# flexi_ethernet_w5500.net
KiCad netlist of a schematic drawn in Altium Designer
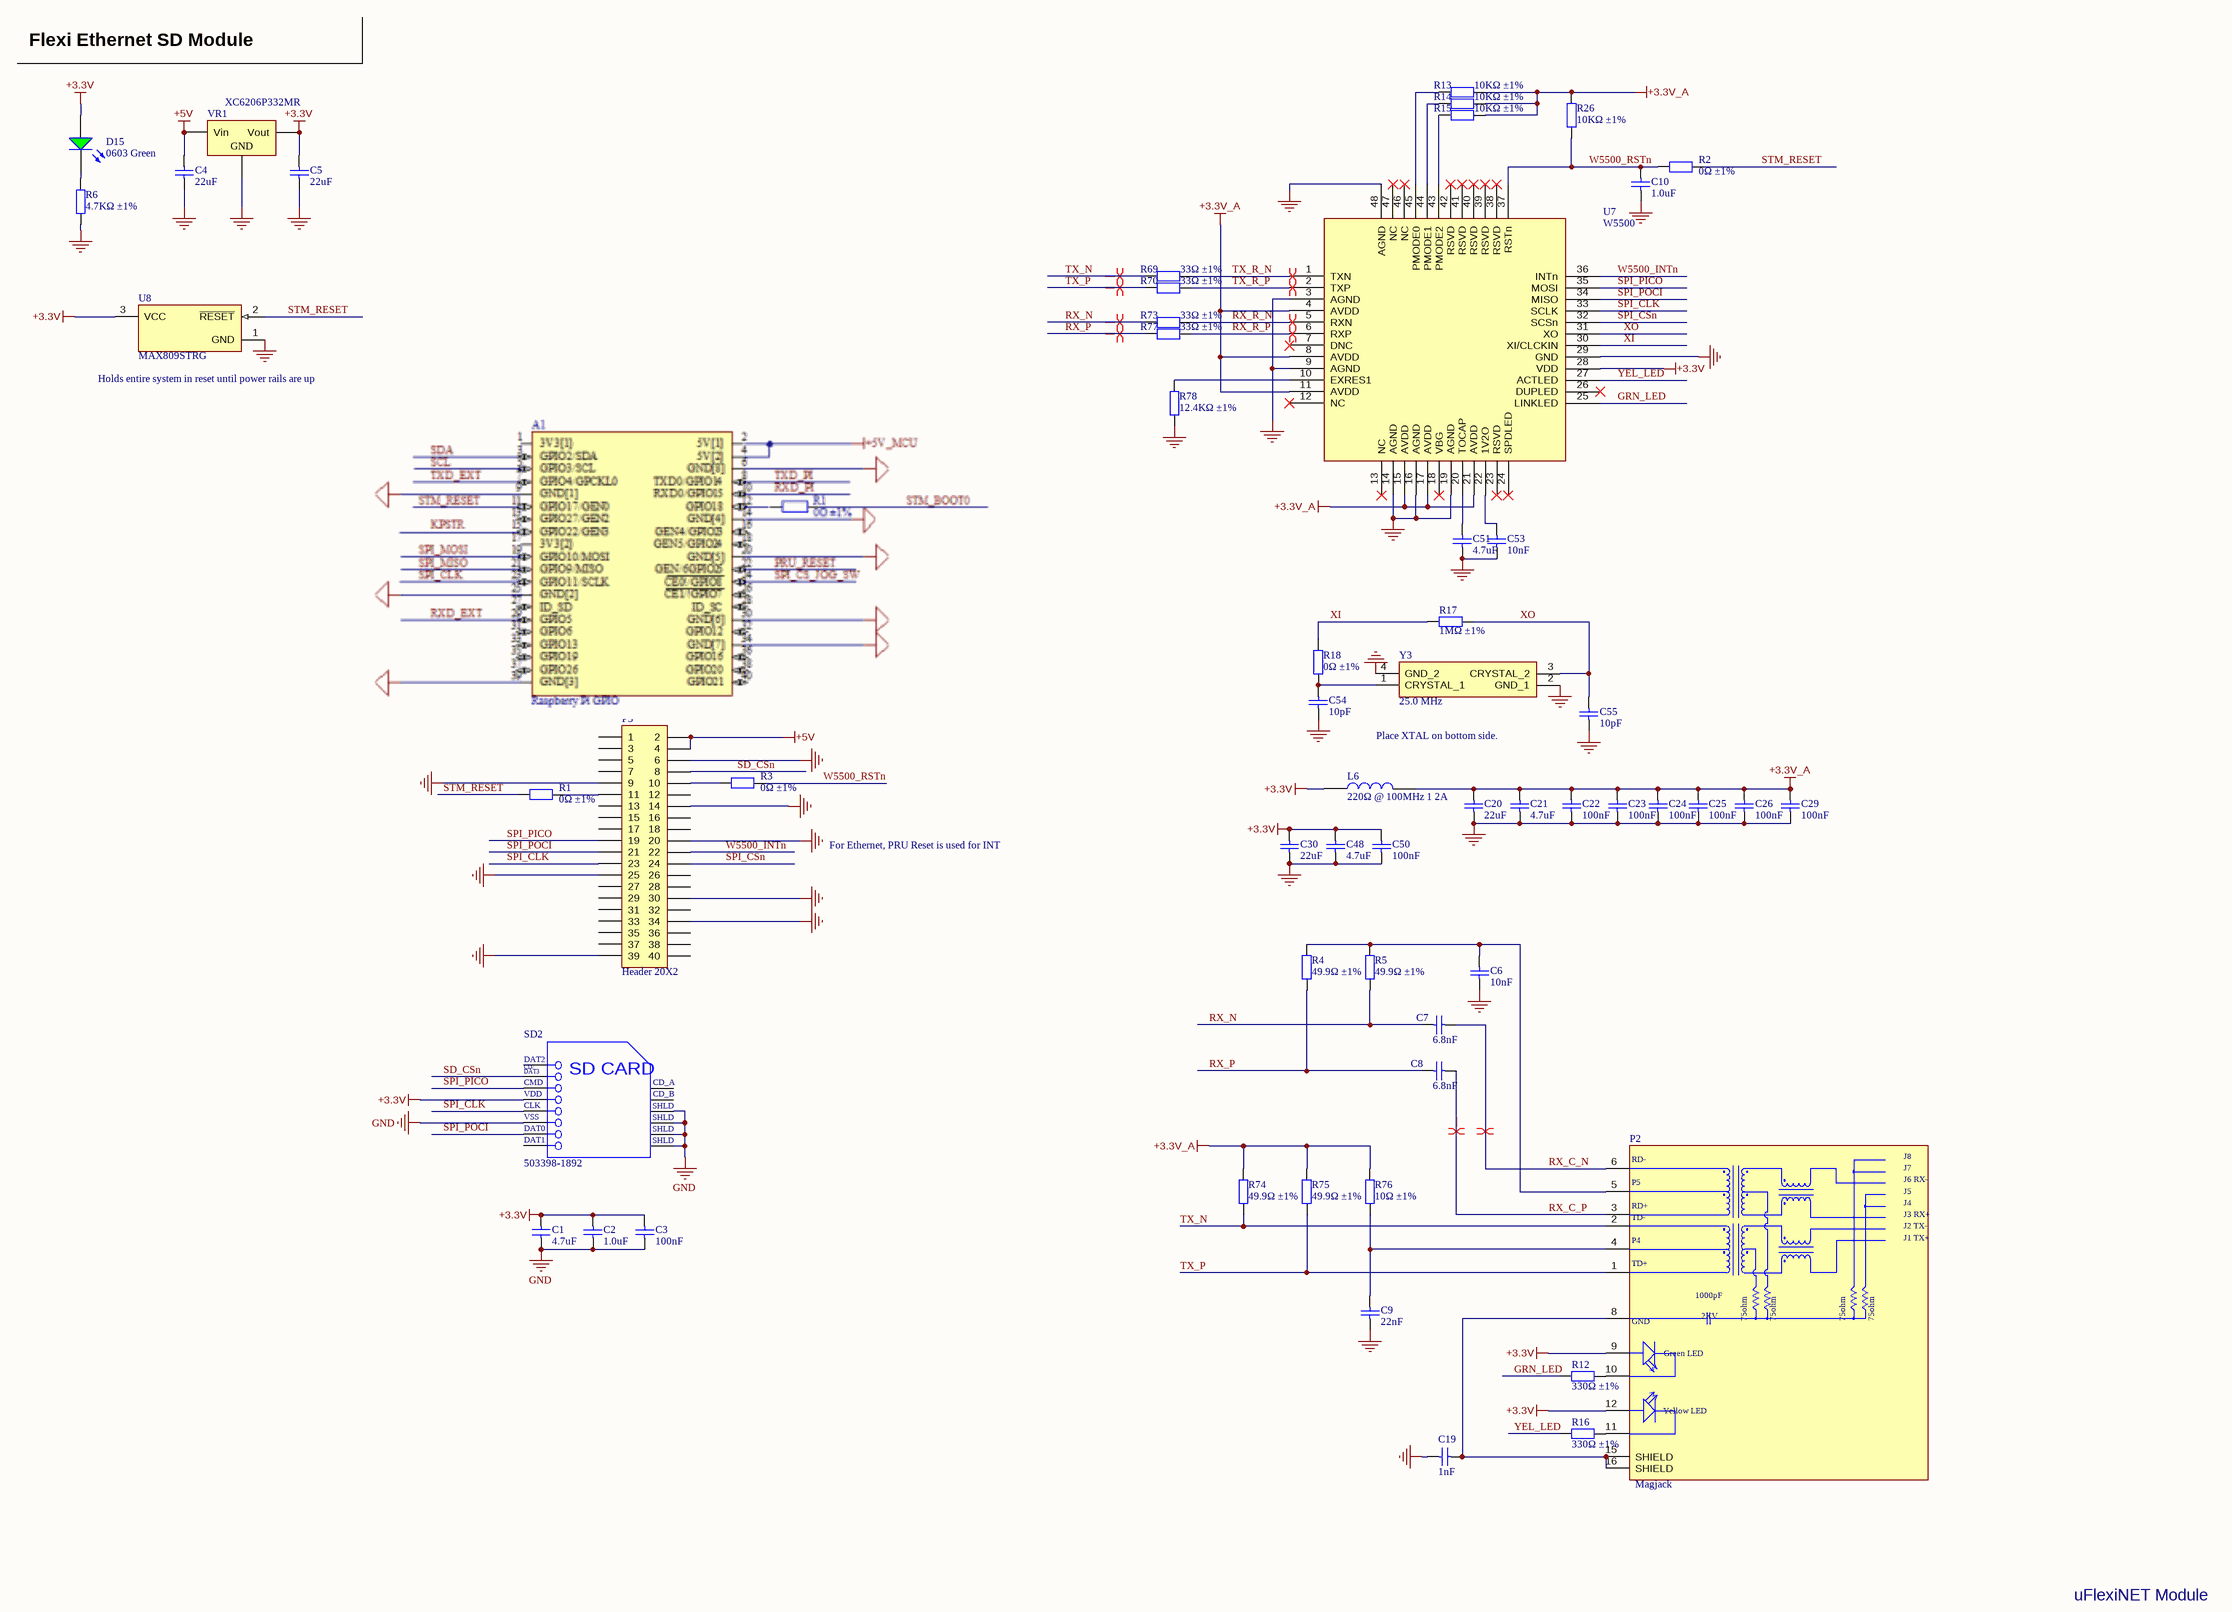
[diagram p0: flexi_ethernet_w5500.SchDoc]

(export (version "E")
  (design (tool "Eeschema 10.0.6"))
  (components
    (comp (ref "C1")
      (value "4.7uF")
      (footprint "0603_C")
      (description "Chip capacitors")
      (fields
        (field (name "MANUFACTURER") "Samsung Electro-Mechanics")
        (field (name "PARTNUMBER") "CL10A475KO8NNNC")
      )
      (libsource (lib "Cap") (part "0603 4.7uF (475) 10% 16V"))
    )
    (comp (ref "C2")
      (value "1.0uF")
      (footprint "0402_C")
      (description "Chip capacitor")
      (fields (field (name "MANUFACTURER") "Samsung Electro-Mechanics") (field (name "TOLERANCE") "10%"))
      (libsource (lib "Cap") (part "0402 1.0uF (105) 10% 25V"))
    )
    (comp (ref "C3")
      (value "100nF")
      (footprint "0402_C")
      (description "Chip capacitors")
      (fields (field (name "MANUFACTURER") "Samsung Electro-Mechanics") (field (name "TOLERANCE") "10%"))
      (libsource (lib "Cap") (part "0402 100nF (104) 10% 16V"))
    )
    (comp (ref "C4")
      (value "22uF")
      (footprint "0805_C")
      (description "Chip capacitors")
      (fields
        (field (name "MANUFACTURER") "Samsung Electro-Mechanics")
        (field (name "PARTNUMBER") "CL21A226MAQNNNE")
      )
      (libsource (lib "Cap") (part "0805 22uF (226) 20% 25V"))
    )
    (comp (ref "C5")
      (value "22uF")
      (footprint "0805_C")
      (description "Chip capacitors")
      (fields
        (field (name "MANUFACTURER") "Samsung Electro-Mechanics")
        (field (name "PARTNUMBER") "CL21A226MAQNNNE")
      )
      (libsource (lib "Cap") (part "0805 22uF (226) 20% 25V"))
    )
    (comp (ref "C6")
      (value "10nF")
      (footprint "0402_C")
      (description "Chip capacitors")
      (fields
        (field (name "MANUFACTURER") "Samsung Electro-Mechanics")
        (field (name "PARTNUMBER") "CL05B103KB5NNNC")
      )
      (libsource (lib "Cap") (part "0402 10nF (103) 10% 50V"))
    )
    (comp (ref "C7")
      (value "6.8nF")
      (footprint "0402_C")
      (description "Chip capacitors")
      (fields
        (field (name "MANUFACTURER") "Guangdong Fenghua Advanced Tech")
        (field (name "PARTNUMBER") "0402B682K500NT")
      )
      (libsource (lib "Cap") (part "0402 6.8nF (682) 10% 50V"))
    )
    (comp (ref "C8")
      (value "6.8nF")
      (footprint "0402_C")
      (description "Chip capacitors")
      (fields
        (field (name "MANUFACTURER") "Guangdong Fenghua Advanced Tech")
        (field (name "PARTNUMBER") "0402B682K500NT")
      )
      (libsource (lib "Cap") (part "0402 6.8nF (682) 10% 50V"))
    )
    (comp (ref "C9")
      (value "22nF")
      (footprint "0402_C")
      (description "Chip capacitors")
      (fields
        (field (name "MANUFACTURER") "Guangdong Fenghua Advanced Tech")
        (field (name "PARTNUMBER") "0402B223K500NT")
      )
      (libsource (lib "Cap") (part "0402 22nF (223) 10% 50V"))
    )
    (comp (ref "C10")
      (value "1.0uF")
      (footprint "0402_C")
      (description "Chip capacitor")
      (fields (field (name "MANUFACTURER") "Samsung Electro-Mechanics") (field (name "TOLERANCE") "10%"))
      (libsource (lib "Cap") (part "0402 1.0uF (105) 10% 25V"))
    )
    (comp (ref "C19")
      (value "1nF")
      (footprint "1206_C")
      (description "Chip capacitors")
      (fields
        (field (name "MANUFACTURER") "Samsung Electro-Mechanics")
        (field (name "PARTNUMBER") "CL31B102KGFNNNE")
      )
      (libsource (lib "Cap") (part "1206 1nF (102) 10% 500V"))
    )
    (comp (ref "C20")
      (value "22uF")
      (footprint "0805_C")
      (description "Chip capacitors")
      (fields
        (field (name "MANUFACTURER") "Samsung Electro-Mechanics")
        (field (name "PARTNUMBER") "CL21A226MAQNNNE")
      )
      (libsource (lib "Cap") (part "0805 22uF (226) 20% 25V"))
    )
    (comp (ref "C21")
      (value "4.7uF")
      (footprint "0603_C")
      (description "Chip capacitors")
      (fields
        (field (name "MANUFACTURER") "Samsung Electro-Mechanics")
        (field (name "PARTNUMBER") "CL10A475KO8NNNC")
      )
      (libsource (lib "Cap") (part "0603 4.7uF (475) 10% 16V"))
    )
    (comp (ref "C22")
      (value "100nF")
      (footprint "0402_C")
      (description "Chip capacitors")
      (fields
        (field (name "MANUFACTURER") "Samsung Electro-Mechanics")
        (field (name "PARTNUMBER") "CL05B104KO5NNNC")
      )
      (libsource (lib "Cap") (part "0402 100nF (104) 10% 16V"))
    )
    (comp (ref "C23")
      (value "100nF")
      (footprint "0402_C")
      (description "Chip capacitors")
      (fields
        (field (name "MANUFACTURER") "Samsung Electro-Mechanics")
        (field (name "PARTNUMBER") "CL05B104KO5NNNC")
      )
      (libsource (lib "Cap") (part "0402 100nF (104) 10% 16V"))
    )
    (comp (ref "C24")
      (value "100nF")
      (footprint "0402_C")
      (description "Chip capacitors")
      (fields
        (field (name "MANUFACTURER") "Samsung Electro-Mechanics")
        (field (name "PARTNUMBER") "CL05B104KO5NNNC")
      )
      (libsource (lib "Cap") (part "0402 100nF (104) 10% 16V"))
    )
    (comp (ref "C25")
      (value "100nF")
      (footprint "0402_C")
      (description "Chip capacitors")
      (fields
        (field (name "MANUFACTURER") "Samsung Electro-Mechanics")
        (field (name "PARTNUMBER") "CL05B104KO5NNNC")
      )
      (libsource (lib "Cap") (part "0402 100nF (104) 10% 16V"))
    )
    (comp (ref "C26")
      (value "100nF")
      (footprint "0402_C")
      (description "Chip capacitors")
      (fields
        (field (name "MANUFACTURER") "Samsung Electro-Mechanics")
        (field (name "PARTNUMBER") "CL05B104KO5NNNC")
      )
      (libsource (lib "Cap") (part "0402 100nF (104) 10% 16V"))
    )
    (comp (ref "C29")
      (value "100nF")
      (footprint "0402_C")
      (description "Chip capacitors")
      (fields
        (field (name "MANUFACTURER") "Samsung Electro-Mechanics")
        (field (name "PARTNUMBER") "CL05B104KO5NNNC")
      )
      (libsource (lib "Cap") (part "0402 100nF (104) 10% 16V"))
    )
    (comp (ref "C30")
      (value "22uF")
      (footprint "0805_C")
      (description "Chip capacitors")
      (fields
        (field (name "MANUFACTURER") "Samsung Electro-Mechanics")
        (field (name "PARTNUMBER") "CL21A226MAQNNNE")
      )
      (libsource (lib "Cap") (part "0805 22uF (226) 20% 25V"))
    )
    (comp (ref "C48")
      (value "4.7uF")
      (footprint "0603_C")
      (description "Chip capacitors")
      (fields
        (field (name "MANUFACTURER") "Samsung Electro-Mechanics")
        (field (name "PARTNUMBER") "CL10A475KO8NNNC")
      )
      (libsource (lib "Cap") (part "0603 4.7uF (475) 10% 16V"))
    )
    (comp (ref "C50")
      (value "100nF")
      (footprint "0402_C")
      (description "Chip capacitors")
      (fields
        (field (name "MANUFACTURER") "Samsung Electro-Mechanics")
        (field (name "PARTNUMBER") "CL05B104KO5NNNC")
      )
      (libsource (lib "Cap") (part "0402 100nF (104) 10% 16V"))
    )
    (comp (ref "C51")
      (value "4.7uF")
      (footprint "0402_C")
      (description "Chip capacitor")
      (fields
        (field (name "MANUFACTURER") "Samsung Electro-Mechanics")
        (field (name "PARTNUMBER") "CL05A475MP5NRNC")
      )
      (libsource (lib "Cap") (part "0402 4.7uF (475) 20% 10V"))
    )
    (comp (ref "C53")
      (value "10nF")
      (footprint "0402_C")
      (description "Chip capacitors")
      (fields
        (field (name "MANUFACTURER") "Samsung Electro-Mechanics")
        (field (name "PARTNUMBER") "CL05B103KB5NNNC")
      )
      (libsource (lib "Cap") (part "0402 10nF (103) 10% 50V"))
    )
    (comp (ref "C54")
      (value "10pF")
      (footprint "0402_C")
      (description "Chip capacitors")
      (fields
        (field (name "MANUFACTURER") "Samsung Electro-Mechanics")
        (field (name "PARTNUMBER") "CL05C100JB5NNNC")
      )
      (libsource (lib "Cap") (part "0402 10pF (100) 5% 50V"))
    )
    (comp (ref "C55")
      (value "10pF")
      (footprint "0402_C")
      (description "Chip capacitors")
      (fields
        (field (name "MANUFACTURER") "Samsung Electro-Mechanics")
        (field (name "PARTNUMBER") "CL05C100JB5NNNC")
      )
      (libsource (lib "Cap") (part "0402 10pF (100) 5% 50V"))
    )
    (comp (ref "D15")
      (value "0603 Green")
      (footprint "0603_LED_S1")
      (description "LED")
      (libsource (lib "LED") (part "0603 LED Green"))
    )
    (comp (ref "L6")
      (value "220Ω @ 100MHz 1 2A")
      (footprint "0805_C")
      (description "220Ω @ 100MHz 1 2A 150mΩ 0805 Ferrite Beads ROHS")
      (libsource (lib "FBEAD") (part "0402 220R@100Mhz 0.1A"))
    )
    (comp (ref "P2")
      (value "Magjack")
      (footprint "HANRUN_HR911105A")
      (description "HR911105A Ethernet Interface Arduino Platform Evaluation Expansion Board")
      (fields (field (name "MP") "HR911105A") (field (name "MF") "DFRobot"))
      (libsource (lib "PrintNC_GRBLHAL_Breakout") (part "HR911105A"))
    )
    (comp (ref "P3")
      (value "Header 20X2")
      (footprint "HDR2X20_2.54_180")
      (description "Header, 20-Pin, Dual row")
      (fields (field (name "PUBLISHER") "Altium Limited"))
      (libsource (lib "Miscellaneous Connectors") (part "Header 20X2"))
    )
    (comp (ref "R1")
      (value "0Ω ±1%")
      (footprint "0402_R")
      (description "Chip resistor")
      (fields (field (name "MANUFACTURER") "Uniroyal Elec") (field (name "PARTNUMBER") "0402WGF0000TCE"))
      (libsource (lib "") (part "0402 0R (0R0) 1%_1"))
    )
    (comp (ref "R2")
      (value "0Ω ±1%")
      (footprint "0402_R")
      (description "Chip resistor")
      (fields (field (name "MANUFACTURER") "Uniroyal Elec") (field (name "PARTNUMBER") "0402WGF0000TCE"))
      (libsource (lib "") (part "0402 0R (0R0) 1%_1"))
    )
    (comp (ref "R3")
      (value "0Ω ±1%")
      (footprint "0402_R")
      (description "Chip resistor")
      (fields (field (name "MANUFACTURER") "Uniroyal Elec") (field (name "PARTNUMBER") "0402WGF0000TCE"))
      (libsource (lib "") (part "0402 0R (0R0) 1%_1"))
    )
    (comp (ref "R4")
      (value "49.9Ω ±1%")
      (footprint "0402_R")
      (description "Chip resistor")
      (fields (field (name "MANUFACTURER") "Uniroyal Elec") (field (name "PARTNUMBER") "0402WGF499JTCE"))
      (libsource (lib "RES") (part "0402 49.9R (49R9) 1%"))
    )
    (comp (ref "R5")
      (value "49.9Ω ±1%")
      (footprint "0402_R")
      (description "Chip resistor")
      (fields (field (name "MANUFACTURER") "Uniroyal Elec") (field (name "PARTNUMBER") "0402WGF499JTCE"))
      (libsource (lib "RES") (part "0402 49.9R (49R9) 1%"))
    )
    (comp (ref "R6")
      (value "4.7KΩ ±1%")
      (footprint "0402_R")
      (description "Chip resistor")
      (fields (field (name "MANUFACTURER") "Uniroyal Elec") (field (name "PARTNUMBER") "0402WGF4701TCE"))
      (libsource (lib "RES") (part "0402 4.7K (4701) 1%"))
    )
    (comp (ref "R12")
      (value "330Ω ±1%")
      (footprint "0402_R")
      (description "Chip resistor")
      (fields (field (name "MANUFACTURER") "Uniroyal Elec") (field (name "PARTNUMBER") "0402WGF3300TCE"))
      (libsource (lib "RES") (part "0402 330R (3300) 1%"))
    )
    (comp (ref "R13")
      (value "10KΩ ±1%")
      (footprint "0402_R")
      (description "Chip resistor")
      (fields (field (name "MANUFACTURER") "Uniroyal Elec") (field (name "PARTNUMBER") "0402WGF1002TCE"))
      (libsource (lib "RES") (part "0402 10K (1002) 1%"))
    )
    (comp (ref "R14")
      (value "10KΩ ±1%")
      (footprint "0402_R")
      (description "Chip resistor")
      (fields (field (name "MANUFACTURER") "Uniroyal Elec") (field (name "PARTNUMBER") "0402WGF1002TCE"))
      (libsource (lib "RES") (part "0402 10K (1002) 1%"))
    )
    (comp (ref "R15")
      (value "10KΩ ±1%")
      (footprint "0402_R")
      (description "Chip resistor")
      (fields (field (name "MANUFACTURER") "Uniroyal Elec") (field (name "PARTNUMBER") "0402WGF1002TCE"))
      (libsource (lib "RES") (part "0402 10K (1002) 1%"))
    )
    (comp (ref "R16")
      (value "330Ω ±1%")
      (footprint "0402_R")
      (description "Chip resistor")
      (fields (field (name "MANUFACTURER") "Uniroyal Elec") (field (name "PARTNUMBER") "0402WGF3300TCE"))
      (libsource (lib "RES") (part "0402 330R (3300) 1%"))
    )
    (comp (ref "R17")
      (value "1MΩ ±1%")
      (footprint "0402_R")
      (description "Chip resistor")
      (fields (field (name "MANUFACTURER") "Uniroyal Elec") (field (name "PARTNUMBER") "0402WGF1004TCE"))
      (libsource (lib "RES") (part "0402 1M (1004) 1%"))
    )
    (comp (ref "R18")
      (value "0Ω ±1%")
      (footprint "0402_R")
      (description "Chip resistor")
      (fields (field (name "MANUFACTURER") "Uniroyal Elec") (field (name "PARTNUMBER") "0402WGF0000TCE"))
      (libsource (lib "RES") (part "0402 0R (0R0) 1%"))
    )
    (comp (ref "R26")
      (value "10KΩ ±1%")
      (footprint "0402_R")
      (description "Chip resistor")
      (fields (field (name "MANUFACTURER") "Uniroyal Elec") (field (name "PARTNUMBER") "0402WGF1002TCE"))
      (libsource (lib "") (part "0402 10K (1002) 1%_1"))
    )
    (comp (ref "R69")
      (value "33Ω ±1%")
      (footprint "0402_R")
      (description "Chip resistor")
      (fields (field (name "MANUFACTURER") "Uniroyal Elec") (field (name "PARTNUMBER") "0402WGF330JTCE"))
      (libsource (lib "RES") (part "0402 33R (33R0) 1%"))
    )
    (comp (ref "R70")
      (value "33Ω ±1%")
      (footprint "0402_R")
      (description "Chip resistor")
      (fields (field (name "MANUFACTURER") "Uniroyal Elec") (field (name "PARTNUMBER") "0402WGF330JTCE"))
      (libsource (lib "RES") (part "0402 33R (33R0) 1%"))
    )
    (comp (ref "R73")
      (value "33Ω ±1%")
      (footprint "0402_R")
      (description "Chip resistor")
      (fields (field (name "MANUFACTURER") "Uniroyal Elec") (field (name "PARTNUMBER") "0402WGF330JTCE"))
      (libsource (lib "RES") (part "0402 33R (33R0) 1%"))
    )
    (comp (ref "R74")
      (value "49.9Ω ±1%")
      (footprint "0402_R")
      (description "Chip resistor")
      (fields (field (name "MANUFACTURER") "Uniroyal Elec") (field (name "PARTNUMBER") "0402WGF499JTCE"))
      (libsource (lib "RES") (part "0402 49.9R (49R9) 1%"))
    )
    (comp (ref "R75")
      (value "49.9Ω ±1%")
      (footprint "0402_R")
      (description "Chip resistor")
      (fields (field (name "MANUFACTURER") "Uniroyal Elec") (field (name "PARTNUMBER") "0402WGF499JTCE"))
      (libsource (lib "RES") (part "0402 49.9R (49R9) 1%"))
    )
    (comp (ref "R76")
      (value "10Ω ±1%")
      (footprint "0402_R")
      (description "Chip resistor")
      (fields (field (name "MANUFACTURER") "Uniroyal Elec") (field (name "PARTNUMBER") "0402WGF100JTCE"))
      (libsource (lib "RES") (part "0402 10R (10R0) 1%"))
    )
    (comp (ref "R77")
      (value "33Ω ±1%")
      (footprint "0402_R")
      (description "Chip resistor")
      (fields (field (name "MANUFACTURER") "Uniroyal Elec") (field (name "PARTNUMBER") "0402WGF330JTCE"))
      (libsource (lib "RES") (part "0402 33R (33R0) 1%"))
    )
    (comp (ref "R78")
      (value "12.4KΩ ±1%")
      (footprint "0603_R")
      (description "Chip resistor")
      (fields (field (name "MANUFACTURER") "Uniroyal Elec") (field (name "PARTNUMBER") "0603WAF1242T5E"))
      (libsource (lib "RES") (part "0603 10K (1002) 1%"))
    )
    (comp (ref "SD2")
      (value "503398-1892")
      (footprint "MOLX-503398-1892_V")
      (description "Micro SD Connector, Pitch 1.1 mm, 8 Position, Height 1.4 mm, -25 to 85 degC, RoHS, Tape and Reel")
      (fields (field (name "MANUFACTURER") "Molex"))
      (libsource (lib "Altium Content Vault") (part "CN-SD-8-2SW-4S"))
    )
    (comp (ref "U7")
      (value "W5500")
      (footprint "LQFP-48_7x7x05P")
      (description "Ethernet Controllers 2.97V ~ 3.63V 10/100 Base-T/TX PHY SPI LQFP-48_7x7x05P Ethernet ICs ROHS")
      (libsource (lib "IC") (part "W5500_[C32843]"))
    )
    (comp (ref "U8")
      (value "MAX809STRG")
      (footprint "FP-318-08-MFG")
      (description "IC MPU SUPERVISORY 2.93V SOT23")
      (fields
        (field (name "OCTOPART") "https://octopart.com/max809strg-on+semiconductor-509853")
        (field (name "MANUFACTURER") "ON SEMICONDUCTOR")
      )
      (libsource (lib "Altium Content Vault") (part "10e2fe7115e7b167e7ed62dcbcd754e"))
    )
    (comp (ref "VR1")
      (value "XC6206P332MR")
      (footprint "SOT-23-3L")
      (description "200mA 680mV@(100mA) Fixed 3.3V~3.3V Positive 1 6V SOT-23-3L Linear Voltage Regulators (LDO) ROHS")
      (libsource (lib "LDO") (part "SOT-23 XC6206P332MR"))
    )
    (comp (ref "Y3")
      (value "25.0 MHz")
      (footprint "SamacSys:YSX321SL")
      (description "Crystal or Oscillator")
      (fields (field (name "MANUFACTURER_PART_NUMBER") "X322525MSB4SI"))
      (libsource (lib "*") (part "YSX321SL"))
    )
  )
  (nets
    (net (code "1") (name "+3.3V") (class "Default")
      (node (ref "C1") (pin "2") (pinfunction "2_2") (pintype "passive"))
      (node (ref "C2") (pin "2") (pinfunction "2_2") (pintype "passive"))
      (node (ref "C3") (pin "2") (pinfunction "2_2") (pintype "passive"))
      (node (ref "C30") (pin "2") (pinfunction "2_2") (pintype "passive"))
      (node (ref "C48") (pin "2") (pinfunction "2_2") (pintype "passive"))
      (node (ref "C5") (pin "2") (pinfunction "2_2") (pintype "passive"))
      (node (ref "C50") (pin "2") (pinfunction "2_2") (pintype "passive"))
      (node (ref "D15") (pin "A") (pinfunction "A_A") (pintype "passive"))
      (node (ref "L6") (pin "1") (pinfunction "1_1") (pintype "passive"))
      (node (ref "P2") (pin "12") (pinfunction "YA_12") (pintype "passive"))
      (node (ref "P2") (pin "9") (pinfunction "GA_9") (pintype "passive"))
      (node (ref "SD2") (pin "4") (pinfunction "VDD_4") (pintype "passive"))
      (node (ref "U7") (pin "28") (pinfunction "VDD_28") (pintype "passive"))
      (node (ref "U8") (pin "3") (pinfunction "VCC_3") (pintype "power_in"))
      (node (ref "VR1") (pin "2") (pinfunction "Vout_2") (pintype "passive"))
    )
    (net (code "2") (name "+3.3V_A") (class "Default")
      (node (ref "C20") (pin "2") (pinfunction "2_2") (pintype "passive"))
      (node (ref "C21") (pin "2") (pinfunction "2_2") (pintype "passive"))
      (node (ref "C22") (pin "2") (pinfunction "2_2") (pintype "passive"))
      (node (ref "C23") (pin "2") (pinfunction "2_2") (pintype "passive"))
      (node (ref "C24") (pin "2") (pinfunction "2_2") (pintype "passive"))
      (node (ref "C25") (pin "2") (pinfunction "2_2") (pintype "passive"))
      (node (ref "C26") (pin "2") (pinfunction "2_2") (pintype "passive"))
      (node (ref "C29") (pin "2") (pinfunction "2_2") (pintype "passive"))
      (node (ref "L6") (pin "2") (pinfunction "2_2") (pintype "passive"))
      (node (ref "R13") (pin "1") (pinfunction "1_1") (pintype "passive"))
      (node (ref "R14") (pin "1") (pinfunction "1_1") (pintype "passive"))
      (node (ref "R15") (pin "1") (pinfunction "1_1") (pintype "passive"))
      (node (ref "R26") (pin "1") (pinfunction "1_1") (pintype "passive"))
      (node (ref "R74") (pin "1") (pinfunction "1_1") (pintype "passive"))
      (node (ref "R75") (pin "1") (pinfunction "1_1") (pintype "passive"))
      (node (ref "R76") (pin "1") (pinfunction "1_1") (pintype "passive"))
      (node (ref "U7") (pin "11") (pinfunction "AVDD_11") (pintype "passive"))
      (node (ref "U7") (pin "15") (pinfunction "AVDD_15") (pintype "passive"))
      (node (ref "U7") (pin "17") (pinfunction "AVDD_17") (pintype "passive"))
      (node (ref "U7") (pin "21") (pinfunction "AVDD_21") (pintype "passive"))
      (node (ref "U7") (pin "4") (pinfunction "AVDD_4") (pintype "passive"))
      (node (ref "U7") (pin "8") (pinfunction "AVDD_8") (pintype "passive"))
    )
    (net (code "3") (name "+5V") (class "Default")
      (node (ref "C4") (pin "2") (pinfunction "2_2") (pintype "passive"))
      (node (ref "P3") (pin "2") (pinfunction "2_2") (pintype "passive"))
      (node (ref "P3") (pin "4") (pinfunction "4_4") (pintype "passive"))
      (node (ref "VR1") (pin "3") (pinfunction "Vin_3") (pintype "passive"))
    )
    (net (code "4") (name "/GRN_LED") (class "Default")
      (node (ref "R12") (pin "1") (pinfunction "1_1") (pintype "passive"))
      (node (ref "U7") (pin "25") (pinfunction "LINKLED_25") (pintype "passive"))
    )
    (net (code "5") (name "/RX_C_N") (class "Default")
      (node (ref "C7") (pin "1") (pinfunction "1_1") (pintype "passive"))
      (node (ref "P2") (pin "6") (pinfunction "RD-_6") (pintype "passive"))
    )
    (net (code "6") (name "/RX_C_P") (class "Default")
      (node (ref "C8") (pin "1") (pinfunction "1_1") (pintype "passive"))
      (node (ref "P2") (pin "3") (pinfunction "RD+_3") (pintype "passive"))
    )
    (net (code "7") (name "/RX_N") (class "Default")
      (node (ref "C7") (pin "2") (pinfunction "2_2") (pintype "passive"))
      (node (ref "R5") (pin "2") (pinfunction "2_2") (pintype "passive"))
      (node (ref "R73") (pin "1") (pinfunction "1_1") (pintype "passive"))
    )
    (net (code "8") (name "/RX_P") (class "Default")
      (node (ref "C8") (pin "2") (pinfunction "2_2") (pintype "passive"))
      (node (ref "R4") (pin "2") (pinfunction "2_2") (pintype "passive"))
      (node (ref "R77") (pin "1") (pinfunction "1_1") (pintype "passive"))
    )
    (net (code "9") (name "/RX_R_N") (class "Default")
      (node (ref "R73") (pin "2") (pinfunction "2_2") (pintype "passive"))
      (node (ref "U7") (pin "5") (pinfunction "RXN_5") (pintype "passive"))
    )
    (net (code "10") (name "/RX_R_P") (class "Default")
      (node (ref "R77") (pin "2") (pinfunction "2_2") (pintype "passive"))
      (node (ref "U7") (pin "6") (pinfunction "RXP_6") (pintype "passive"))
    )
    (net (code "11") (name "/SD_CSn") (class "Default")
      (node (ref "P3") (pin "8") (pinfunction "8_8") (pintype "passive"))
      (node (ref "SD2") (pin "2") (pinfunction "CD/DAT3_2") (pintype "passive"))
    )
    (net (code "12") (name "/SPI_CLK") (class "Default")
      (node (ref "P3") (pin "23") (pinfunction "23_23") (pintype "passive"))
      (node (ref "SD2") (pin "5") (pinfunction "CLK_5") (pintype "passive"))
      (node (ref "U7") (pin "33") (pinfunction "SCLK_33") (pintype "passive"))
    )
    (net (code "13") (name "/SPI_CSn") (class "Default")
      (node (ref "P3") (pin "24") (pinfunction "24_24") (pintype "passive"))
      (node (ref "U7") (pin "32") (pinfunction "SCSn_32") (pintype "passive"))
    )
    (net (code "14") (name "/SPI_PICO") (class "Default")
      (node (ref "P3") (pin "19") (pinfunction "19_19") (pintype "passive"))
      (node (ref "SD2") (pin "3") (pinfunction "CMD_3") (pintype "passive"))
      (node (ref "U7") (pin "35") (pinfunction "MOSI_35") (pintype "passive"))
    )
    (net (code "15") (name "/SPI_POCI") (class "Default")
      (node (ref "P3") (pin "21") (pinfunction "21_21") (pintype "passive"))
      (node (ref "SD2") (pin "7") (pinfunction "DAT0_7") (pintype "passive"))
      (node (ref "U7") (pin "34") (pinfunction "MISO_34") (pintype "passive"))
    )
    (net (code "16") (name "/STM_RESET") (class "Default")
      (node (ref "R1") (pin "2") (pinfunction "2_2") (pintype "passive"))
      (node (ref "R2") (pin "1") (pinfunction "1_1") (pintype "passive"))
      (node (ref "U8") (pin "2") (pinfunction "~{RESET}_2") (pintype "input"))
    )
    (net (code "17") (name "/TX_N") (class "Default")
      (node (ref "P2") (pin "2") (pinfunction "TD-_2") (pintype "passive"))
      (node (ref "R69") (pin "1") (pinfunction "1_1") (pintype "passive"))
      (node (ref "R74") (pin "2") (pinfunction "2_2") (pintype "passive"))
    )
    (net (code "18") (name "/TX_P") (class "Default")
      (node (ref "P2") (pin "1") (pinfunction "TD+_1") (pintype "passive"))
      (node (ref "R70") (pin "1") (pinfunction "1_1") (pintype "passive"))
      (node (ref "R75") (pin "2") (pinfunction "2_2") (pintype "passive"))
    )
    (net (code "19") (name "/TX_R_N") (class "Default")
      (node (ref "R69") (pin "2") (pinfunction "2_2") (pintype "passive"))
      (node (ref "U7") (pin "1") (pinfunction "TXN_1") (pintype "passive"))
    )
    (net (code "20") (name "/TX_R_P") (class "Default")
      (node (ref "R70") (pin "2") (pinfunction "2_2") (pintype "passive"))
      (node (ref "U7") (pin "2") (pinfunction "TXP_2") (pintype "passive"))
    )
    (net (code "21") (name "/W5500_INTn") (class "Default")
      (node (ref "P3") (pin "22") (pinfunction "22_22") (pintype "passive"))
      (node (ref "U7") (pin "36") (pinfunction "INTn_36") (pintype "passive"))
    )
    (net (code "22") (name "/W5500_RSTn") (class "Default")
      (node (ref "C10") (pin "2") (pinfunction "2_2") (pintype "passive"))
      (node (ref "R2") (pin "2") (pinfunction "2_2") (pintype "passive"))
      (node (ref "R26") (pin "2") (pinfunction "2_2") (pintype "passive"))
      (node (ref "R3") (pin "1") (pinfunction "1_1") (pintype "passive"))
      (node (ref "U7") (pin "37") (pinfunction "RSTn_37") (pintype "passive"))
    )
    (net (code "23") (name "/XI") (class "Default")
      (node (ref "R17") (pin "1") (pinfunction "1_1") (pintype "passive"))
      (node (ref "R18") (pin "1") (pinfunction "1_1") (pintype "passive"))
      (node (ref "U7") (pin "30") (pinfunction "XI/CLCKIN_30") (pintype "passive"))
    )
    (net (code "24") (name "/XO") (class "Default")
      (node (ref "C55") (pin "2") (pinfunction "2_2") (pintype "passive"))
      (node (ref "R17") (pin "2") (pinfunction "2_2") (pintype "passive"))
      (node (ref "U7") (pin "31") (pinfunction "XO_31") (pintype "passive"))
      (node (ref "Y3") (pin "3") (pinfunction "CRYSTAL_2_3") (pintype "passive"))
    )
    (net (code "25") (name "/YEL_LED") (class "Default")
      (node (ref "R16") (pin "1") (pinfunction "1_1") (pintype "passive"))
      (node (ref "U7") (pin "27") (pinfunction "ACTLED_27") (pintype "passive"))
    )
    (net (code "26") (name "GND") (class "Default")
      (node (ref "C1") (pin "1") (pinfunction "1_1") (pintype "passive"))
      (node (ref "C10") (pin "1") (pinfunction "1_1") (pintype "passive"))
      (node (ref "C19") (pin "1") (pinfunction "1_1") (pintype "passive"))
      (node (ref "C2") (pin "1") (pinfunction "1_1") (pintype "passive"))
      (node (ref "C20") (pin "1") (pinfunction "1_1") (pintype "passive"))
      (node (ref "C21") (pin "1") (pinfunction "1_1") (pintype "passive"))
      (node (ref "C22") (pin "1") (pinfunction "1_1") (pintype "passive"))
      (node (ref "C23") (pin "1") (pinfunction "1_1") (pintype "passive"))
      (node (ref "C24") (pin "1") (pinfunction "1_1") (pintype "passive"))
      (node (ref "C25") (pin "1") (pinfunction "1_1") (pintype "passive"))
      (node (ref "C26") (pin "1") (pinfunction "1_1") (pintype "passive"))
      (node (ref "C29") (pin "1") (pinfunction "1_1") (pintype "passive"))
      (node (ref "C3") (pin "1") (pinfunction "1_1") (pintype "passive"))
      (node (ref "C30") (pin "1") (pinfunction "1_1") (pintype "passive"))
      (node (ref "C4") (pin "1") (pinfunction "1_1") (pintype "passive"))
      (node (ref "C48") (pin "1") (pinfunction "1_1") (pintype "passive"))
      (node (ref "C5") (pin "1") (pinfunction "1_1") (pintype "passive"))
      (node (ref "C50") (pin "1") (pinfunction "1_1") (pintype "passive"))
      (node (ref "C51") (pin "1") (pinfunction "1_1") (pintype "passive"))
      (node (ref "C53") (pin "1") (pinfunction "1_1") (pintype "passive"))
      (node (ref "C54") (pin "1") (pinfunction "1_1") (pintype "passive"))
      (node (ref "C55") (pin "1") (pinfunction "1_1") (pintype "passive"))
      (node (ref "C6") (pin "1") (pinfunction "1_1") (pintype "passive"))
      (node (ref "C9") (pin "1") (pinfunction "1_1") (pintype "passive"))
      (node (ref "P3") (pin "14") (pinfunction "14_14") (pintype "passive"))
      (node (ref "P3") (pin "20") (pinfunction "20_20") (pintype "passive"))
      (node (ref "P3") (pin "25") (pinfunction "25_25") (pintype "passive"))
      (node (ref "P3") (pin "30") (pinfunction "30_30") (pintype "passive"))
      (node (ref "P3") (pin "34") (pinfunction "34_34") (pintype "passive"))
      (node (ref "P3") (pin "39") (pinfunction "39_39") (pintype "passive"))
      (node (ref "P3") (pin "6") (pinfunction "6_6") (pintype "passive"))
      (node (ref "P3") (pin "9") (pinfunction "9_9") (pintype "passive"))
      (node (ref "R6") (pin "1") (pinfunction "1_1") (pintype "passive"))
      (node (ref "R78") (pin "1") (pinfunction "1_1") (pintype "passive"))
      (node (ref "SD2") (pin "11") (pinfunction "SHLD_11") (pintype "passive"))
      (node (ref "SD2") (pin "12") (pinfunction "SHLD_12") (pintype "passive"))
      (node (ref "SD2") (pin "13") (pinfunction "SHLD_13") (pintype "passive"))
      (node (ref "SD2") (pin "14") (pinfunction "SHLD_14") (pintype "passive"))
      (node (ref "SD2") (pin "6") (pinfunction "VSS_6") (pintype "passive"))
      (node (ref "U7") (pin "14") (pinfunction "AGND_14") (pintype "passive"))
      (node (ref "U7") (pin "16") (pinfunction "AGND_16") (pintype "passive"))
      (node (ref "U7") (pin "19") (pinfunction "AGND_19") (pintype "passive"))
      (node (ref "U7") (pin "29") (pinfunction "GND_29") (pintype "passive"))
      (node (ref "U7") (pin "3") (pinfunction "AGND_3") (pintype "passive"))
      (node (ref "U7") (pin "48") (pinfunction "AGND_48") (pintype "passive"))
      (node (ref "U7") (pin "9") (pinfunction "AGND_9") (pintype "passive"))
      (node (ref "U8") (pin "1") (pinfunction "GND_1") (pintype "power_in"))
      (node (ref "VR1") (pin "1") (pinfunction "GND_1") (pintype "passive"))
      (node (ref "Y3") (pin "2") (pinfunction "GND_1_2") (pintype "passive"))
      (node (ref "Y3") (pin "4") (pinfunction "GND_2_4") (pintype "passive"))
    )
    (net (code "27") (name "Net-(D15-PadK)") (class "Default")
      (node (ref "D15") (pin "K") (pinfunction "K_K") (pintype "passive"))
      (node (ref "R6") (pin "2") (pinfunction "2_2") (pintype "passive"))
    )
    (net (code "28") (name "Net-(P2-GC)") (class "Default")
      (node (ref "P2") (pin "10") (pinfunction "GC_10") (pintype "passive"))
      (node (ref "R12") (pin "2") (pinfunction "2_2") (pintype "passive"))
    )
    (net (code "29") (name "Net-(P2-GND)") (class "Default")
      (node (ref "C19") (pin "2") (pinfunction "2_2") (pintype "passive"))
      (node (ref "P2") (pin "15") (pinfunction "SHIELD_15") (pintype "passive"))
      (node (ref "P2") (pin "16") (pinfunction "SHIELD_16") (pintype "passive"))
      (node (ref "P2") (pin "8") (pinfunction "GND_8") (pintype "power_in"))
    )
    (net (code "30") (name "Net-(P2-P4)") (class "Default")
      (node (ref "C9") (pin "2") (pinfunction "2_2") (pintype "passive"))
      (node (ref "P2") (pin "4") (pinfunction "P4_4") (pintype "passive"))
      (node (ref "R76") (pin "2") (pinfunction "2_2") (pintype "passive"))
    )
    (net (code "31") (name "Net-(P2-P5)") (class "Default")
      (node (ref "C6") (pin "2") (pinfunction "2_2") (pintype "passive"))
      (node (ref "P2") (pin "5") (pinfunction "P5_5") (pintype "passive"))
      (node (ref "R4") (pin "1") (pinfunction "1_1") (pintype "passive"))
      (node (ref "R5") (pin "1") (pinfunction "1_1") (pintype "passive"))
    )
    (net (code "32") (name "Net-(P2-YC)") (class "Default")
      (node (ref "P2") (pin "11") (pinfunction "YC_11") (pintype "passive"))
      (node (ref "R16") (pin "2") (pinfunction "2_2") (pintype "passive"))
    )
    (net (code "33") (name "Net-(P3-Pad10)") (class "Default")
      (node (ref "P3") (pin "10") (pinfunction "10_10") (pintype "passive"))
      (node (ref "R3") (pin "2") (pinfunction "2_2") (pintype "passive"))
    )
    (net (code "34") (name "Net-(P3-Pad11)") (class "Default")
      (node (ref "P3") (pin "11") (pinfunction "11_11") (pintype "passive"))
      (node (ref "R1") (pin "1") (pinfunction "1_1") (pintype "passive"))
    )
    (net (code "35") (name "Net-(U7-1V2O)") (class "Default")
      (node (ref "C53") (pin "2") (pinfunction "2_2") (pintype "passive"))
      (node (ref "U7") (pin "22") (pinfunction "1V2O_22") (pintype "passive"))
    )
    (net (code "36") (name "Net-(U7-EXRES1)") (class "Default")
      (node (ref "R78") (pin "2") (pinfunction "2_2") (pintype "passive"))
      (node (ref "U7") (pin "10") (pinfunction "EXRES1_10") (pintype "passive"))
    )
    (net (code "37") (name "Net-(U7-PMODE0)") (class "Default")
      (node (ref "R13") (pin "2") (pinfunction "2_2") (pintype "passive"))
      (node (ref "U7") (pin "45") (pinfunction "PMODE0_45") (pintype "passive"))
    )
    (net (code "38") (name "Net-(U7-PMODE1)") (class "Default")
      (node (ref "R14") (pin "2") (pinfunction "2_2") (pintype "passive"))
      (node (ref "U7") (pin "44") (pinfunction "PMODE1_44") (pintype "passive"))
    )
    (net (code "39") (name "Net-(U7-PMODE2)") (class "Default")
      (node (ref "R15") (pin "2") (pinfunction "2_2") (pintype "passive"))
      (node (ref "U7") (pin "43") (pinfunction "PMODE2_43") (pintype "passive"))
    )
    (net (code "40") (name "Net-(U7-TOCAP)") (class "Default")
      (node (ref "C51") (pin "2") (pinfunction "2_2") (pintype "passive"))
      (node (ref "U7") (pin "20") (pinfunction "TOCAP_20") (pintype "passive"))
    )
    (net (code "41") (name "Net-(Y3-CRYSTAL_1)") (class "Default")
      (node (ref "C54") (pin "2") (pinfunction "2_2") (pintype "passive"))
      (node (ref "R18") (pin "2") (pinfunction "2_2") (pintype "passive"))
      (node (ref "Y3") (pin "1") (pinfunction "CRYSTAL_1_1") (pintype "passive"))
    )
    (net (code "42") (name "unconnected-(P3-Pad1)") (class "Default")
      (node (ref "P3") (pin "1") (pinfunction "1_1") (pintype "passive"))
    )
    (net (code "43") (name "unconnected-(P3-Pad3)") (class "Default")
      (node (ref "P3") (pin "3") (pinfunction "3_3") (pintype "passive"))
    )
    (net (code "44") (name "unconnected-(P3-Pad5)") (class "Default")
      (node (ref "P3") (pin "5") (pinfunction "5_5") (pintype "passive"))
    )
    (net (code "45") (name "unconnected-(P3-Pad7)") (class "Default")
      (node (ref "P3") (pin "7") (pinfunction "7_7") (pintype "passive"))
    )
    (net (code "46") (name "unconnected-(P3-Pad12)") (class "Default")
      (node (ref "P3") (pin "12") (pinfunction "12_12") (pintype "passive"))
    )
    (net (code "47") (name "unconnected-(P3-Pad13)") (class "Default")
      (node (ref "P3") (pin "13") (pinfunction "13_13") (pintype "passive"))
    )
    (net (code "48") (name "unconnected-(P3-Pad15)") (class "Default")
      (node (ref "P3") (pin "15") (pinfunction "15_15") (pintype "passive"))
    )
    (net (code "49") (name "unconnected-(P3-Pad16)") (class "Default")
      (node (ref "P3") (pin "16") (pinfunction "16_16") (pintype "passive"))
    )
    (net (code "50") (name "unconnected-(P3-Pad17)") (class "Default")
      (node (ref "P3") (pin "17") (pinfunction "17_17") (pintype "passive"))
    )
    (net (code "51") (name "unconnected-(P3-Pad18)") (class "Default")
      (node (ref "P3") (pin "18") (pinfunction "18_18") (pintype "passive"))
    )
    (net (code "52") (name "unconnected-(P3-Pad26)") (class "Default")
      (node (ref "P3") (pin "26") (pinfunction "26_26") (pintype "passive"))
    )
    (net (code "53") (name "unconnected-(P3-Pad27)") (class "Default")
      (node (ref "P3") (pin "27") (pinfunction "27_27") (pintype "passive"))
    )
    (net (code "54") (name "unconnected-(P3-Pad28)") (class "Default")
      (node (ref "P3") (pin "28") (pinfunction "28_28") (pintype "passive"))
    )
    (net (code "55") (name "unconnected-(P3-Pad29)") (class "Default")
      (node (ref "P3") (pin "29") (pinfunction "29_29") (pintype "passive"))
    )
    (net (code "56") (name "unconnected-(P3-Pad31)") (class "Default")
      (node (ref "P3") (pin "31") (pinfunction "31_31") (pintype "passive"))
    )
    (net (code "57") (name "unconnected-(P3-Pad32)") (class "Default")
      (node (ref "P3") (pin "32") (pinfunction "32_32") (pintype "passive"))
    )
    (net (code "58") (name "unconnected-(P3-Pad33)") (class "Default")
      (node (ref "P3") (pin "33") (pinfunction "33_33") (pintype "passive"))
    )
    (net (code "59") (name "unconnected-(P3-Pad35)") (class "Default")
      (node (ref "P3") (pin "35") (pinfunction "35_35") (pintype "passive"))
    )
    (net (code "60") (name "unconnected-(P3-Pad36)") (class "Default")
      (node (ref "P3") (pin "36") (pinfunction "36_36") (pintype "passive"))
    )
    (net (code "61") (name "unconnected-(P3-Pad37)") (class "Default")
      (node (ref "P3") (pin "37") (pinfunction "37_37") (pintype "passive"))
    )
    (net (code "62") (name "unconnected-(P3-Pad38)") (class "Default")
      (node (ref "P3") (pin "38") (pinfunction "38_38") (pintype "passive"))
    )
    (net (code "63") (name "unconnected-(P3-Pad40)") (class "Default")
      (node (ref "P3") (pin "40") (pinfunction "40_40") (pintype "passive"))
    )
    (net (code "64") (name "unconnected-(SD2-CD_A-Pad9)") (class "Default")
      (node (ref "SD2") (pin "9") (pinfunction "CD_A_9") (pintype "passive"))
    )
    (net (code "65") (name "unconnected-(SD2-CD_B-Pad10)") (class "Default")
      (node (ref "SD2") (pin "10") (pinfunction "CD_B_10") (pintype "passive"))
    )
    (net (code "66") (name "unconnected-(SD2-DAT1-Pad8)") (class "Default")
      (node (ref "SD2") (pin "8") (pinfunction "DAT1_8") (pintype "passive"))
    )
    (net (code "67") (name "unconnected-(SD2-DAT2-Pad1)") (class "Default")
      (node (ref "SD2") (pin "1") (pinfunction "DAT2_1") (pintype "passive"))
    )
    (net (code "68") (name "unconnected-(U7-DNC-Pad7)") (class "Default")
      (node (ref "U7") (pin "7") (pinfunction "DNC_7") (pintype "passive+no_connect"))
    )
    (net (code "69") (name "unconnected-(U7-DUPLED-Pad26)") (class "Default")
      (node (ref "U7") (pin "26") (pinfunction "DUPLED_26") (pintype "passive+no_connect"))
    )
    (net (code "70") (name "unconnected-(U7-NC-Pad12)") (class "Default")
      (node (ref "U7") (pin "12") (pinfunction "NC_12") (pintype "passive+no_connect"))
    )
    (net (code "71") (name "unconnected-(U7-NC-Pad13)") (class "Default")
      (node (ref "U7") (pin "13") (pinfunction "NC_13") (pintype "passive+no_connect"))
    )
    (net (code "72") (name "unconnected-(U7-NC-Pad46)") (class "Default")
      (node (ref "U7") (pin "46") (pinfunction "NC_46") (pintype "passive+no_connect"))
    )
    (net (code "73") (name "unconnected-(U7-NC-Pad47)") (class "Default")
      (node (ref "U7") (pin "47") (pinfunction "NC_47") (pintype "passive+no_connect"))
    )
    (net (code "74") (name "unconnected-(U7-RSVD-Pad23)") (class "Default")
      (node (ref "U7") (pin "23") (pinfunction "RSVD_23") (pintype "passive+no_connect"))
    )
    (net (code "75") (name "unconnected-(U7-RSVD-Pad38)") (class "Default")
      (node (ref "U7") (pin "38") (pinfunction "RSVD_38") (pintype "passive+no_connect"))
    )
    (net (code "76") (name "unconnected-(U7-RSVD-Pad39)") (class "Default")
      (node (ref "U7") (pin "39") (pinfunction "RSVD_39") (pintype "passive+no_connect"))
    )
    (net (code "77") (name "unconnected-(U7-RSVD-Pad40)") (class "Default")
      (node (ref "U7") (pin "40") (pinfunction "RSVD_40") (pintype "passive+no_connect"))
    )
    (net (code "78") (name "unconnected-(U7-RSVD-Pad41)") (class "Default")
      (node (ref "U7") (pin "41") (pinfunction "RSVD_41") (pintype "passive+no_connect"))
    )
    (net (code "79") (name "unconnected-(U7-RSVD-Pad42)") (class "Default")
      (node (ref "U7") (pin "42") (pinfunction "RSVD_42") (pintype "passive+no_connect"))
    )
    (net (code "80") (name "unconnected-(U7-SPDLED-Pad24)") (class "Default")
      (node (ref "U7") (pin "24") (pinfunction "SPDLED_24") (pintype "passive+no_connect"))
    )
    (net (code "81") (name "unconnected-(U7-VBG-Pad18)") (class "Default")
      (node (ref "U7") (pin "18") (pinfunction "VBG_18") (pintype "passive+no_connect"))
    )
  )
)
